# 3_AASTM32-Peripheral.net
KiCad netlist of a schematic drawn in Altium Designer
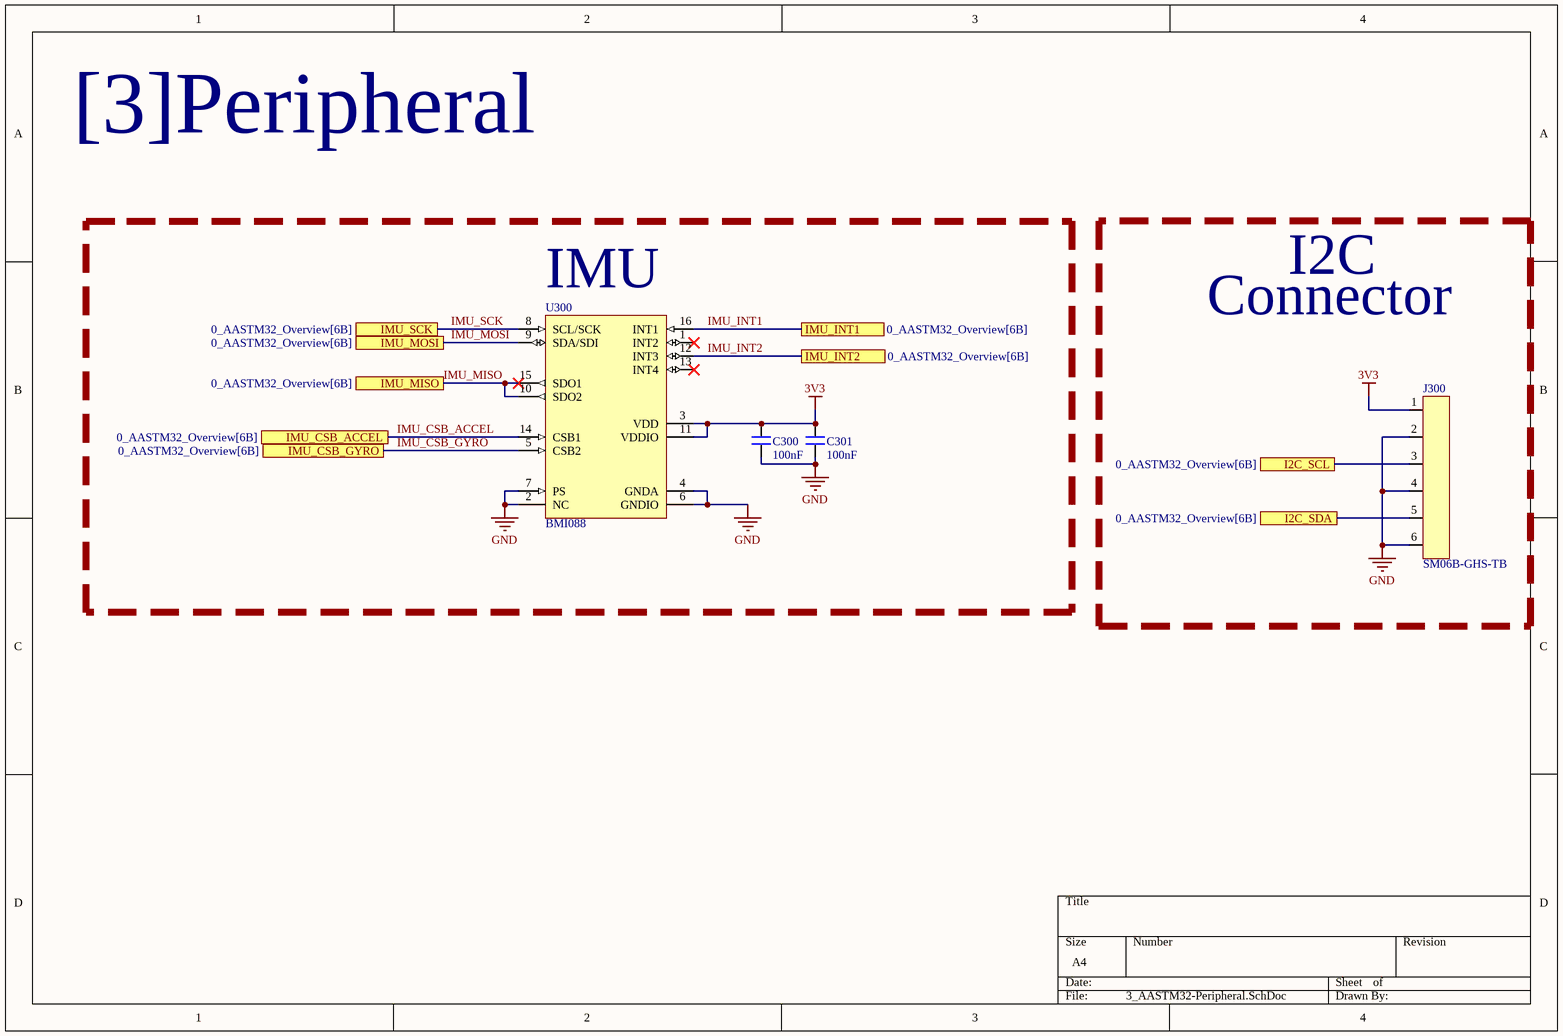
[diagram p0: 3_AASTM32-Peripheral.SchDoc]

(export (version "E")
  (design (tool "Eeschema 10.0.6"))
  (components
    (comp (ref "C300")
      (value "100nF")
      (footprint "0603 CAP")
      (fields
        (field (name "MANUFACTURER") "Samsung")
        (field (name "MANUFACTURER PART NUMBER") "CL10A475KA8NQNC")
      )
      (libsource (lib "GenerALI") (part "0603 4u7 CAP"))
    )
    (comp (ref "C301")
      (value "100nF")
      (footprint "0603 CAP")
      (fields
        (field (name "MANUFACTURER") "Samsung")
        (field (name "MANUFACTURER PART NUMBER") "CL10A475KA8NQNC")
      )
      (libsource (lib "GenerALI") (part "0603 4u7 CAP"))
    )
    (comp (ref "J300")
      (value "SM06B-GHS-TB")
      (footprint "SM06B-GHS-TB")
      (description "Header Connector 6 Position 1.25MM Pitch SMD Horizontal JST GH")
      (fields (field (name "MANUFACTURER") "JST"))
      (libsource (lib "Schematic-Lib-PhilsLab") (part "SM06B-GHS-TB"))
    )
    (comp (ref "U300")
      (value "BMI088")
      (footprint "LGA-16 BOSCH")
      (fields (field (name "MANUFACTURER") "Bosch Sensortec"))
      (libsource (lib "GenerALI") (part "BMI088"))
    )
  )
  (nets
    (net (code "1") (name "/I2C_SCL") (class "Default")
      (node (ref "J300") (pin "3") (pinfunction "3_3") (pintype "passive"))
    )
    (net (code "2") (name "/I2C_SDA") (class "Default")
      (node (ref "J300") (pin "5") (pinfunction "5_5") (pintype "passive"))
    )
    (net (code "3") (name "/IMU_CSB_ACCEL") (class "Default")
      (node (ref "U300") (pin "14") (pinfunction "CSB1_14") (pintype "input"))
    )
    (net (code "4") (name "/IMU_CSB_GYRO") (class "Default")
      (node (ref "U300") (pin "5") (pinfunction "CSB2_5") (pintype "input"))
    )
    (net (code "5") (name "/IMU_INT1") (class "Default")
      (node (ref "U300") (pin "16") (pinfunction "INT1_16") (pintype "input"))
    )
    (net (code "6") (name "/IMU_INT2") (class "Default")
      (node (ref "U300") (pin "12") (pinfunction "INT3_12") (pintype "bidirectional"))
    )
    (net (code "7") (name "/IMU_MISO") (class "Default")
      (node (ref "U300") (pin "10") (pinfunction "SDO2_10") (pintype "output"))
      (node (ref "U300") (pin "15") (pinfunction "SDO1_15") (pintype "output"))
    )
    (net (code "8") (name "/IMU_MOSI") (class "Default")
      (node (ref "U300") (pin "9") (pinfunction "SDA/SDI_9") (pintype "bidirectional"))
    )
    (net (code "9") (name "/IMU_SCK") (class "Default")
      (node (ref "U300") (pin "8") (pinfunction "SCL/SCK_8") (pintype "input"))
    )
    (net (code "10") (name "3V3") (class "Default")
      (node (ref "C300") (pin "2") (pinfunction "2_2") (pintype "passive"))
      (node (ref "C301") (pin "2") (pinfunction "2_2") (pintype "passive"))
      (node (ref "J300") (pin "1") (pinfunction "1_1") (pintype "passive"))
      (node (ref "U300") (pin "11") (pinfunction "VDDIO_11") (pintype "power_in"))
      (node (ref "U300") (pin "3") (pinfunction "VDD_3") (pintype "power_in"))
    )
    (net (code "11") (name "GND") (class "Default")
      (node (ref "C300") (pin "1") (pinfunction "1_1") (pintype "passive"))
      (node (ref "C301") (pin "1") (pinfunction "1_1") (pintype "passive"))
      (node (ref "J300") (pin "2") (pinfunction "2_2") (pintype "passive"))
      (node (ref "J300") (pin "4") (pinfunction "4_4") (pintype "passive"))
      (node (ref "J300") (pin "6") (pinfunction "6_6") (pintype "passive"))
      (node (ref "U300") (pin "2") (pinfunction "NC_2") (pintype "passive"))
      (node (ref "U300") (pin "4") (pinfunction "GNDA_4") (pintype "power_in"))
      (node (ref "U300") (pin "6") (pinfunction "GNDIO_6") (pintype "power_in"))
      (node (ref "U300") (pin "7") (pinfunction "PS_7") (pintype "input"))
    )
    (net (code "12") (name "unconnected-(U300-INT2-Pad1)") (class "Default")
      (node (ref "U300") (pin "1") (pinfunction "INT2_1") (pintype "bidirectional+no_connect"))
    )
    (net (code "13") (name "unconnected-(U300-INT4-Pad13)") (class "Default")
      (node (ref "U300") (pin "13") (pinfunction "INT4_13") (pintype "bidirectional+no_connect"))
    )
  )
)
